# dribbler.net
KiCad netlist of a schematic drawn in EAGLE
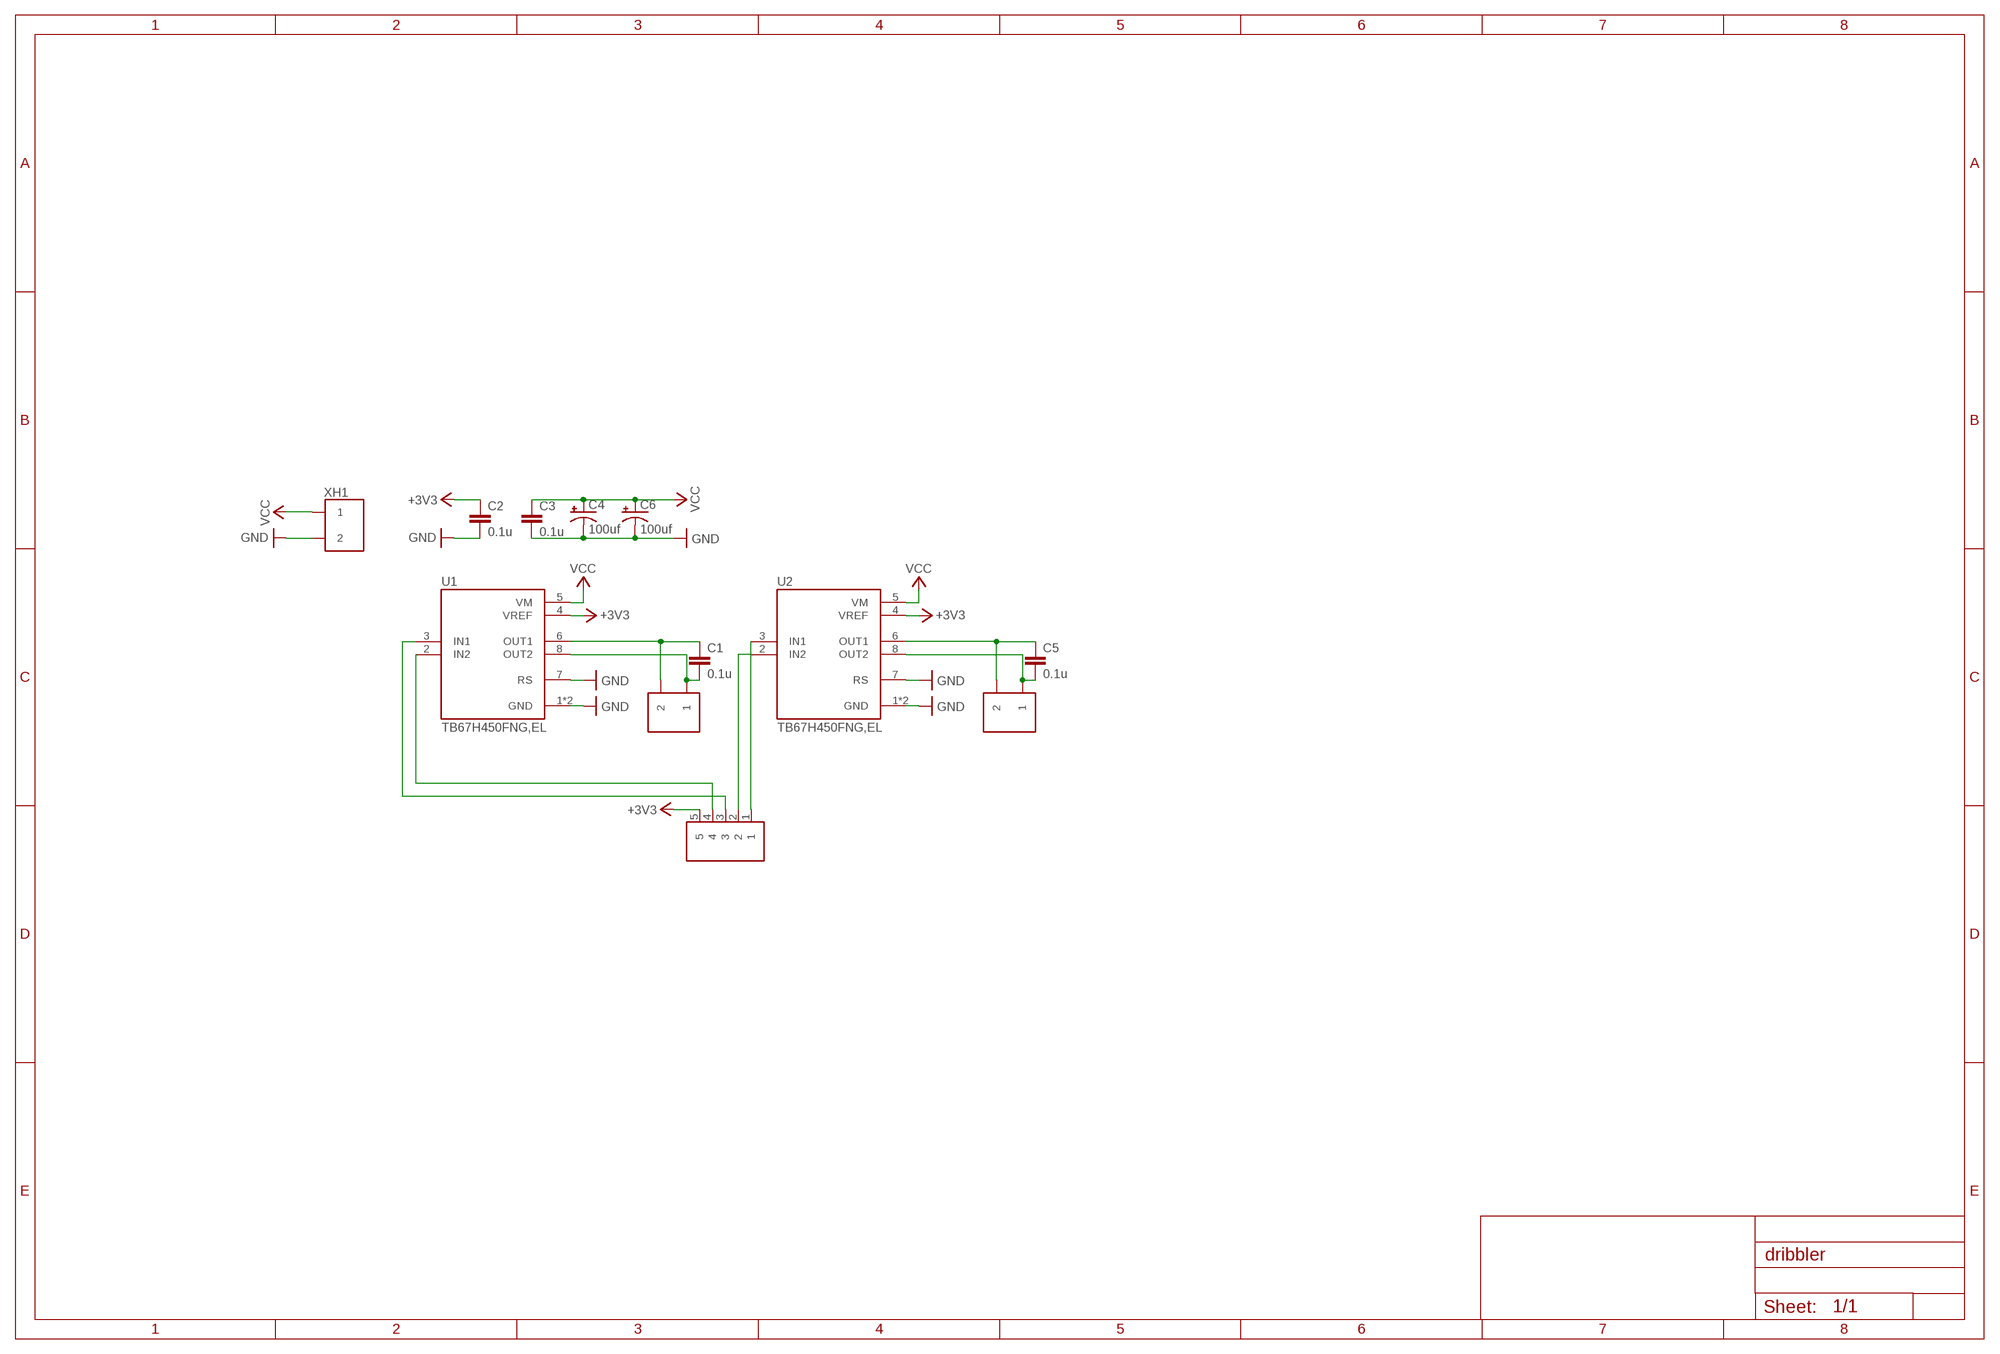
[diagram p0: schematic, sheet 1]

(export (version "E")
  (design (tool "Eeschema 10.0.6"))
  (components
    (comp (ref "C1")
      (value "0.1u")
      (footprint "eagle-import:C0603")
      (libsource (lib "eagle-import") (part "C-EUC0603"))
    )
    (comp (ref "C2")
      (value "0.1u")
      (footprint "eagle-import:C0603")
      (libsource (lib "eagle-import") (part "C-EUC0603"))
    )
    (comp (ref "C3")
      (value "0.1u")
      (footprint "eagle-import:C0603")
      (libsource (lib "eagle-import") (part "C-EUC0603"))
    )
    (comp (ref "C4")
      (value "100uf")
      (footprint "eagle-import:MH5")
      (libsource (lib "eagle-import") (part "MH5"))
    )
    (comp (ref "C5")
      (value "0.1u")
      (footprint "eagle-import:C0603")
      (libsource (lib "eagle-import") (part "C-EUC0603"))
    )
    (comp (ref "C6")
      (value "100uf")
      (footprint "eagle-import:MH5")
      (libsource (lib "eagle-import") (part "MH5"))
    )
    (comp (ref "U$1")
      (value "S2B")
      (footprint "eagle-import:S2B")
      (libsource (lib "eagle-import") (part "S2B"))
    )
    (comp (ref "U$2")
      (value "S5B")
      (footprint "eagle-import:S5B")
      (libsource (lib "eagle-import") (part "S5B"))
    )
    (comp (ref "U$3")
      (value "S2B")
      (footprint "eagle-import:S2B")
      (libsource (lib "eagle-import") (part "S2B"))
    )
    (comp (ref "U1")
      (value "TB67H450FNG,EL")
      (footprint "eagle-import:SOIC127P599X175-9N")
      (fields (field (name "MF") "Toshiba Semiconductor and Storage"))
      (libsource (lib "eagle-import") (part "TB67H450FNG,EL"))
    )
    (comp (ref "U2")
      (value "TB67H450FNG,EL")
      (footprint "eagle-import:SOIC127P599X175-9N")
      (fields (field (name "MF") "Toshiba Semiconductor and Storage"))
      (libsource (lib "eagle-import") (part "TB67H450FNG,EL"))
    )
    (comp (ref "XH1")
      (value "S2B")
      (footprint "eagle-import:S2B")
      (libsource (lib "eagle-import") (part "S2B"))
    )
  )
  (nets
    (net (code "1") (name "+3V3") (class "Default")
      (node (ref "C2") (pin "1") (pinfunction "1_1") (pintype "passive"))
      (node (ref "U$2") (pin "5") (pinfunction "5_5") (pintype "bidirectional"))
      (node (ref "U1") (pin "4") (pinfunction "VREF_4") (pintype "power_in"))
      (node (ref "U2") (pin "4") (pinfunction "VREF_4") (pintype "power_in"))
    )
    (net (code "2") (name "GND") (class "Default")
      (node (ref "C2") (pin "2") (pinfunction "2_2") (pintype "passive"))
      (node (ref "C3") (pin "2") (pinfunction "2_2") (pintype "passive"))
      (node (ref "C4") (pin "-") (pinfunction "-_-") (pintype "passive"))
      (node (ref "C6") (pin "-") (pinfunction "-_-") (pintype "passive"))
      (node (ref "U1") (pin "1") (pinfunction "GND_1") (pintype "power_in"))
      (node (ref "U1") (pin "7") (pinfunction "RS_7") (pintype "output"))
      (node (ref "U1") (pin "9") (pinfunction "GND_9") (pintype "power_in"))
      (node (ref "U2") (pin "1") (pinfunction "GND_1") (pintype "power_in"))
      (node (ref "U2") (pin "7") (pinfunction "RS_7") (pintype "output"))
      (node (ref "U2") (pin "9") (pinfunction "GND_9") (pintype "power_in"))
      (node (ref "XH1") (pin "2") (pinfunction "2_2") (pintype "bidirectional"))
    )
    (net (code "3") (name "Net-(U1-IN1)") (class "Default")
      (node (ref "U$2") (pin "3") (pinfunction "3_3") (pintype "bidirectional"))
      (node (ref "U1") (pin "3") (pinfunction "IN1_3") (pintype "input"))
    )
    (net (code "4") (name "Net-(U1-IN2)") (class "Default")
      (node (ref "U$2") (pin "4") (pinfunction "4_4") (pintype "bidirectional"))
      (node (ref "U1") (pin "2") (pinfunction "IN2_2") (pintype "input"))
    )
    (net (code "5") (name "Net-(U1-OUT1)") (class "Default")
      (node (ref "C1") (pin "1") (pinfunction "1_1") (pintype "passive"))
      (node (ref "U$1") (pin "2") (pinfunction "2_2") (pintype "bidirectional"))
      (node (ref "U1") (pin "6") (pinfunction "OUT1_6") (pintype "output"))
    )
    (net (code "6") (name "Net-(U1-OUT2)") (class "Default")
      (node (ref "C1") (pin "2") (pinfunction "2_2") (pintype "passive"))
      (node (ref "U$1") (pin "1") (pinfunction "1_1") (pintype "bidirectional"))
      (node (ref "U1") (pin "8") (pinfunction "OUT2_8") (pintype "output"))
    )
    (net (code "7") (name "Net-(U2-IN1)") (class "Default")
      (node (ref "U$2") (pin "1") (pinfunction "1_1") (pintype "bidirectional"))
      (node (ref "U2") (pin "3") (pinfunction "IN1_3") (pintype "input"))
    )
    (net (code "8") (name "Net-(U2-IN2)") (class "Default")
      (node (ref "U$2") (pin "2") (pinfunction "2_2") (pintype "bidirectional"))
      (node (ref "U2") (pin "2") (pinfunction "IN2_2") (pintype "input"))
    )
    (net (code "9") (name "Net-(U2-OUT1)") (class "Default")
      (node (ref "C5") (pin "1") (pinfunction "1_1") (pintype "passive"))
      (node (ref "U$3") (pin "2") (pinfunction "2_2") (pintype "bidirectional"))
      (node (ref "U2") (pin "6") (pinfunction "OUT1_6") (pintype "output"))
    )
    (net (code "10") (name "Net-(U2-OUT2)") (class "Default")
      (node (ref "C5") (pin "2") (pinfunction "2_2") (pintype "passive"))
      (node (ref "U$3") (pin "1") (pinfunction "1_1") (pintype "bidirectional"))
      (node (ref "U2") (pin "8") (pinfunction "OUT2_8") (pintype "output"))
    )
    (net (code "11") (name "VCC") (class "Default")
      (node (ref "C3") (pin "1") (pinfunction "1_1") (pintype "passive"))
      (node (ref "C4") (pin "+") (pinfunction "+_+") (pintype "passive"))
      (node (ref "C6") (pin "+") (pinfunction "+_+") (pintype "passive"))
      (node (ref "U1") (pin "5") (pinfunction "VM_5") (pintype "power_in"))
      (node (ref "U2") (pin "5") (pinfunction "VM_5") (pintype "power_in"))
      (node (ref "XH1") (pin "1") (pinfunction "1_1") (pintype "bidirectional"))
    )
  )
)
